# PA_8CH_USER_IFC.net
KiCad netlist of a schematic drawn in Altium Designer
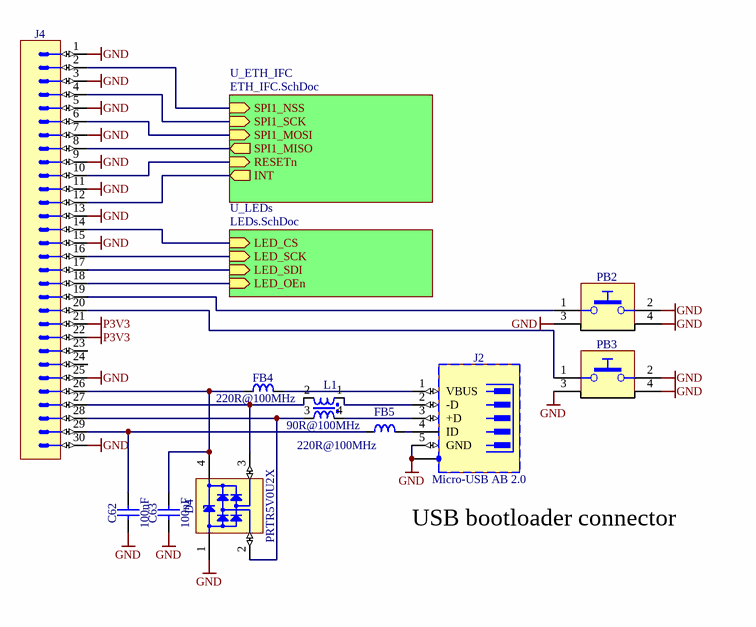
[diagram p0: PA_8CH_USER_IFC.SchDoc]

(export (version "E")
  (design (tool "Eeschema 10.0.6"))
  (components
    (comp (ref "C62")
      (value "100nF")
      (footprint "CAPC1005X55N")
      (description "Non-polarised capacitor")
      (fields
        (field (name "PART NUMBER") "CC0402_100NF_16V_10%_X7R")
        (field (name "VOLTAGE") "16V")
        (field (name "AUTHOR") "CERN DEM JLC")
      )
      (libsource (lib "Capacitors") (part "Capacitor - non polarized"))
    )
    (comp (ref "C63")
      (value "100nF")
      (footprint "CAPC1005X55N")
      (description "Non-polarised capacitor")
      (fields
        (field (name "PART NUMBER") "CC0402_100NF_16V_10%_X7R")
        (field (name "VOLTAGE") "16V")
        (field (name "AUTHOR") "CERN DEM JLC")
      )
      (libsource (lib "Capacitors") (part "Capacitor - non polarized"))
    )
    (comp (ref "D4")
      (value "PRTR5V0U2X")
      (footprint "SOT190P230X110-4N")
      (description "Ultra Low Capacitance Double Rail-to-Rail ESD Protection Diode")
      (fields
        (field (name "VOLTAGE") "5.5V")
        (field (name "MANUFACTURER") "NXP SEMICONDUCTORS")
        (field (name "AUTHOR") "CERN DEM JLC")
      )
      (libsource (lib "ICs And Semiconductors") (part "PRTR5V0U2X"))
    )
    (comp (ref "FB4")
      (value "220R@100MHz")
      (footprint "INDC2012X105N")
      (description "Inductor")
      (fields
        (field (name "PART NUMBER") "IND0805_MURATA_BLM21PG221SN1D")
        (field (name "POWER") "2A")
        (field (name "AUTHOR") "CERN DEM JLC")
      )
      (libsource (lib "Inductors & Transformers") (part "Inductor"))
    )
    (comp (ref "FB5")
      (value "220R@100MHz")
      (footprint "INDC2012X105N")
      (description "Inductor")
      (fields
        (field (name "PART NUMBER") "IND0805_MURATA_BLM21PG221SN1D")
        (field (name "POWER") "2A")
        (field (name "AUTHOR") "CERN DEM JLC")
      )
      (libsource (lib "Inductors & Transformers") (part "Inductor"))
    )
    (comp (ref "J2")
      (value "Micro-USB AB 2.0")
      (footprint "HIROSE_ZX62RD-AB-5P8")
      (description "5 Pin + 1 Shield USB Receptacle")
      (fields
        (field (name "PART NUMBER") "HIROSE_ZX62RD-AB-5P8")
        (field (name "MANUFACTURER") "HIROSE (HRS)")
        (field (name "AUTHOR") "CERN DEM JLC")
      )
      (libsource (lib "Connectors") (part "Connector USB 5 Pin + 1Shield"))
    )
    (comp (ref "J4")
      (value "~")
      (footprint "3M_N2530-6002RB")
      (description "Connector 30 Male")
      (fields
        (field (name "PART NUMBER") "3M_N2530-6002RB")
        (field (name "MANUFACTURER") "3M")
        (field (name "AUTHOR") "CERN DEM JLC")
      )
      (libsource (lib "Connectors") (part "Connector 30 Male"))
    )
    (comp (ref "L1")
      (value "90R@100MHz")
      (footprint "IND_MURATA_DLW21S")
      (description "Inductor Common Mode")
      (fields
        (field (name "PART NUMBER") "IND_MURATA_DLW21SN900SQ2L")
        (field (name "POWER") "330mA")
        (field (name "AUTHOR") "CERN DEM JLC")
      )
      (libsource (lib "Inductors & Transformers") (part "Inductor Common Mode 1Dot-2 4Dot-3"))
    )
    (comp (ref "PB2")
      (value "Push Button")
      (footprint "PB_TYCO_1-1825027-1")
      (description "Push-Button Switch SPDT")
      (fields
        (field (name "PART NUMBER") "PB_TYCO_1-1825027-1")
        (field (name "MANUFACTURER") "TYCO ELECTRONICS")
        (field (name "AUTHOR") "CERN DEM JLC")
      )
      (libsource (lib "Eletro-mechanical") (part "PB SPST 1NO-2NO 34CASE"))
    )
    (comp (ref "PB3")
      (value "Push Button")
      (footprint "PB_TYCO_1-1825027-1")
      (description "Push-Button Switch SPDT")
      (fields
        (field (name "PART NUMBER") "PB_TYCO_1-1825027-1")
        (field (name "MANUFACTURER") "TYCO ELECTRONICS")
        (field (name "AUTHOR") "CERN DEM JLC")
      )
      (libsource (lib "Eletro-mechanical") (part "PB SPST 1NO-2NO 34CASE"))
    )
  )
  (nets
    (net (code "1") (name "/INT") (class "Default")
      (node (ref "J4") (pin "12") (pinfunction "12_12") (pintype "bidirectional"))
    )
    (net (code "2") (name "/LED_CS") (class "Default")
      (node (ref "J4") (pin "14") (pinfunction "14_14") (pintype "bidirectional"))
    )
    (net (code "3") (name "/LED_OEn") (class "Default")
      (node (ref "J4") (pin "18") (pinfunction "18_18") (pintype "bidirectional"))
    )
    (net (code "4") (name "/LED_SCK") (class "Default")
      (node (ref "J4") (pin "16") (pinfunction "16_16") (pintype "bidirectional"))
    )
    (net (code "5") (name "/LED_SDI") (class "Default")
      (node (ref "J4") (pin "17") (pinfunction "17_17") (pintype "bidirectional"))
    )
    (net (code "6") (name "/RESETn") (class "Default")
      (node (ref "J4") (pin "10") (pinfunction "10_10") (pintype "bidirectional"))
    )
    (net (code "7") (name "/SPI1_MISO") (class "Default")
      (node (ref "J4") (pin "8") (pinfunction "8_8") (pintype "bidirectional"))
    )
    (net (code "8") (name "/SPI1_MOSI") (class "Default")
      (node (ref "J4") (pin "6") (pinfunction "6_6") (pintype "bidirectional"))
    )
    (net (code "9") (name "/SPI1_NSS") (class "Default")
      (node (ref "J4") (pin "2") (pinfunction "2_2") (pintype "bidirectional"))
    )
    (net (code "10") (name "/SPI1_SCK") (class "Default")
      (node (ref "J4") (pin "4") (pinfunction "4_4") (pintype "bidirectional"))
    )
    (net (code "11") (name "GND") (class "Default")
      (node (ref "C62") (pin "1") (pinfunction "1_1") (pintype "passive"))
      (node (ref "C63") (pin "1") (pinfunction "1_1") (pintype "passive"))
      (node (ref "D4") (pin "1") (pinfunction "GND_1") (pintype "power_in"))
      (node (ref "J2") (pin "5") (pinfunction "GND_5") (pintype "bidirectional"))
      (node (ref "J2") (pin "6") (pinfunction "SH_6") (pintype "power_in"))
      (node (ref "J4") (pin "1") (pinfunction "1_1") (pintype "bidirectional"))
      (node (ref "J4") (pin "11") (pinfunction "11_11") (pintype "bidirectional"))
      (node (ref "J4") (pin "13") (pinfunction "13_13") (pintype "bidirectional"))
      (node (ref "J4") (pin "15") (pinfunction "15_15") (pintype "bidirectional"))
      (node (ref "J4") (pin "25") (pinfunction "25_25") (pintype "bidirectional"))
      (node (ref "J4") (pin "3") (pinfunction "3_3") (pintype "bidirectional"))
      (node (ref "J4") (pin "30") (pinfunction "30_30") (pintype "bidirectional"))
      (node (ref "J4") (pin "5") (pinfunction "5_5") (pintype "bidirectional"))
      (node (ref "J4") (pin "7") (pinfunction "7_7") (pintype "bidirectional"))
      (node (ref "J4") (pin "9") (pinfunction "9_9") (pintype "bidirectional"))
      (node (ref "PB2") (pin "2") (pinfunction "2_2") (pintype "passive"))
      (node (ref "PB2") (pin "3") (pinfunction "3_3") (pintype "passive"))
      (node (ref "PB2") (pin "4") (pinfunction "4_4") (pintype "passive"))
      (node (ref "PB3") (pin "2") (pinfunction "2_2") (pintype "passive"))
      (node (ref "PB3") (pin "3") (pinfunction "3_3") (pintype "passive"))
      (node (ref "PB3") (pin "4") (pinfunction "4_4") (pintype "passive"))
    )
    (net (code "12") (name "Net-(C62-Pad2)") (class "Default")
      (node (ref "C62") (pin "2") (pinfunction "2_2") (pintype "passive"))
      (node (ref "FB5") (pin "1") (pinfunction "1_1") (pintype "passive"))
      (node (ref "J4") (pin "29") (pinfunction "29_29") (pintype "bidirectional"))
    )
    (net (code "13") (name "Net-(D4-I{slash}O1)") (class "Default")
      (node (ref "D4") (pin "2") (pinfunction "I/O1_2") (pintype "bidirectional"))
      (node (ref "J4") (pin "28") (pinfunction "28_28") (pintype "bidirectional"))
      (node (ref "L1") (pin "3") (pinfunction "3_3") (pintype "passive"))
    )
    (net (code "14") (name "Net-(D4-I{slash}O2)") (class "Default")
      (node (ref "D4") (pin "3") (pinfunction "I/O2_3") (pintype "bidirectional"))
      (node (ref "J4") (pin "27") (pinfunction "27_27") (pintype "bidirectional"))
      (node (ref "L1") (pin "2") (pinfunction "2_2") (pintype "passive"))
    )
    (net (code "15") (name "Net-(D4-VCC)") (class "Default")
      (node (ref "C63") (pin "2") (pinfunction "2_2") (pintype "passive"))
      (node (ref "D4") (pin "4") (pinfunction "VCC_4") (pintype "power_in"))
      (node (ref "FB4") (pin "1") (pinfunction "1_1") (pintype "passive"))
      (node (ref "J4") (pin "26") (pinfunction "26_26") (pintype "bidirectional"))
    )
    (net (code "16") (name "Net-(J2-+D)") (class "Default")
      (node (ref "J2") (pin "3") (pinfunction "+D_3") (pintype "bidirectional"))
      (node (ref "L1") (pin "4") (pinfunction "4_4") (pintype "passive"))
    )
    (net (code "17") (name "Net-(J2--D)") (class "Default")
      (node (ref "J2") (pin "2") (pinfunction "-D_2") (pintype "bidirectional"))
      (node (ref "L1") (pin "1") (pinfunction "1_1") (pintype "passive"))
    )
    (net (code "18") (name "Net-(J2-ID)") (class "Default")
      (node (ref "FB5") (pin "2") (pinfunction "2_2") (pintype "passive"))
      (node (ref "J2") (pin "4") (pinfunction "ID_4") (pintype "passive"))
    )
    (net (code "19") (name "Net-(J2-VBUS)") (class "Default")
      (node (ref "FB4") (pin "2") (pinfunction "2_2") (pintype "passive"))
      (node (ref "J2") (pin "1") (pinfunction "VBUS_1") (pintype "bidirectional"))
    )
    (net (code "20") (name "Net-(J4-Pad19)") (class "Default")
      (node (ref "J4") (pin "19") (pinfunction "19_19") (pintype "bidirectional"))
      (node (ref "PB2") (pin "1") (pinfunction "1_1") (pintype "passive"))
    )
    (net (code "21") (name "Net-(J4-Pad20)") (class "Default")
      (node (ref "J4") (pin "20") (pinfunction "20_20") (pintype "bidirectional"))
      (node (ref "PB3") (pin "1") (pinfunction "1_1") (pintype "passive"))
    )
    (net (code "22") (name "P3V3") (class "Default")
      (node (ref "J4") (pin "21") (pinfunction "21_21") (pintype "bidirectional"))
      (node (ref "J4") (pin "22") (pinfunction "22_22") (pintype "bidirectional"))
    )
    (net (code "23") (name "unconnected-(J4-Pad23)") (class "Default")
      (node (ref "J4") (pin "23") (pinfunction "23_23") (pintype "bidirectional"))
    )
    (net (code "24") (name "unconnected-(J4-Pad24)") (class "Default")
      (node (ref "J4") (pin "24") (pinfunction "24_24") (pintype "bidirectional"))
    )
  )
)
